# 611_jetbot_010210.net
KiCad netlist of a schematic drawn in EAGLE
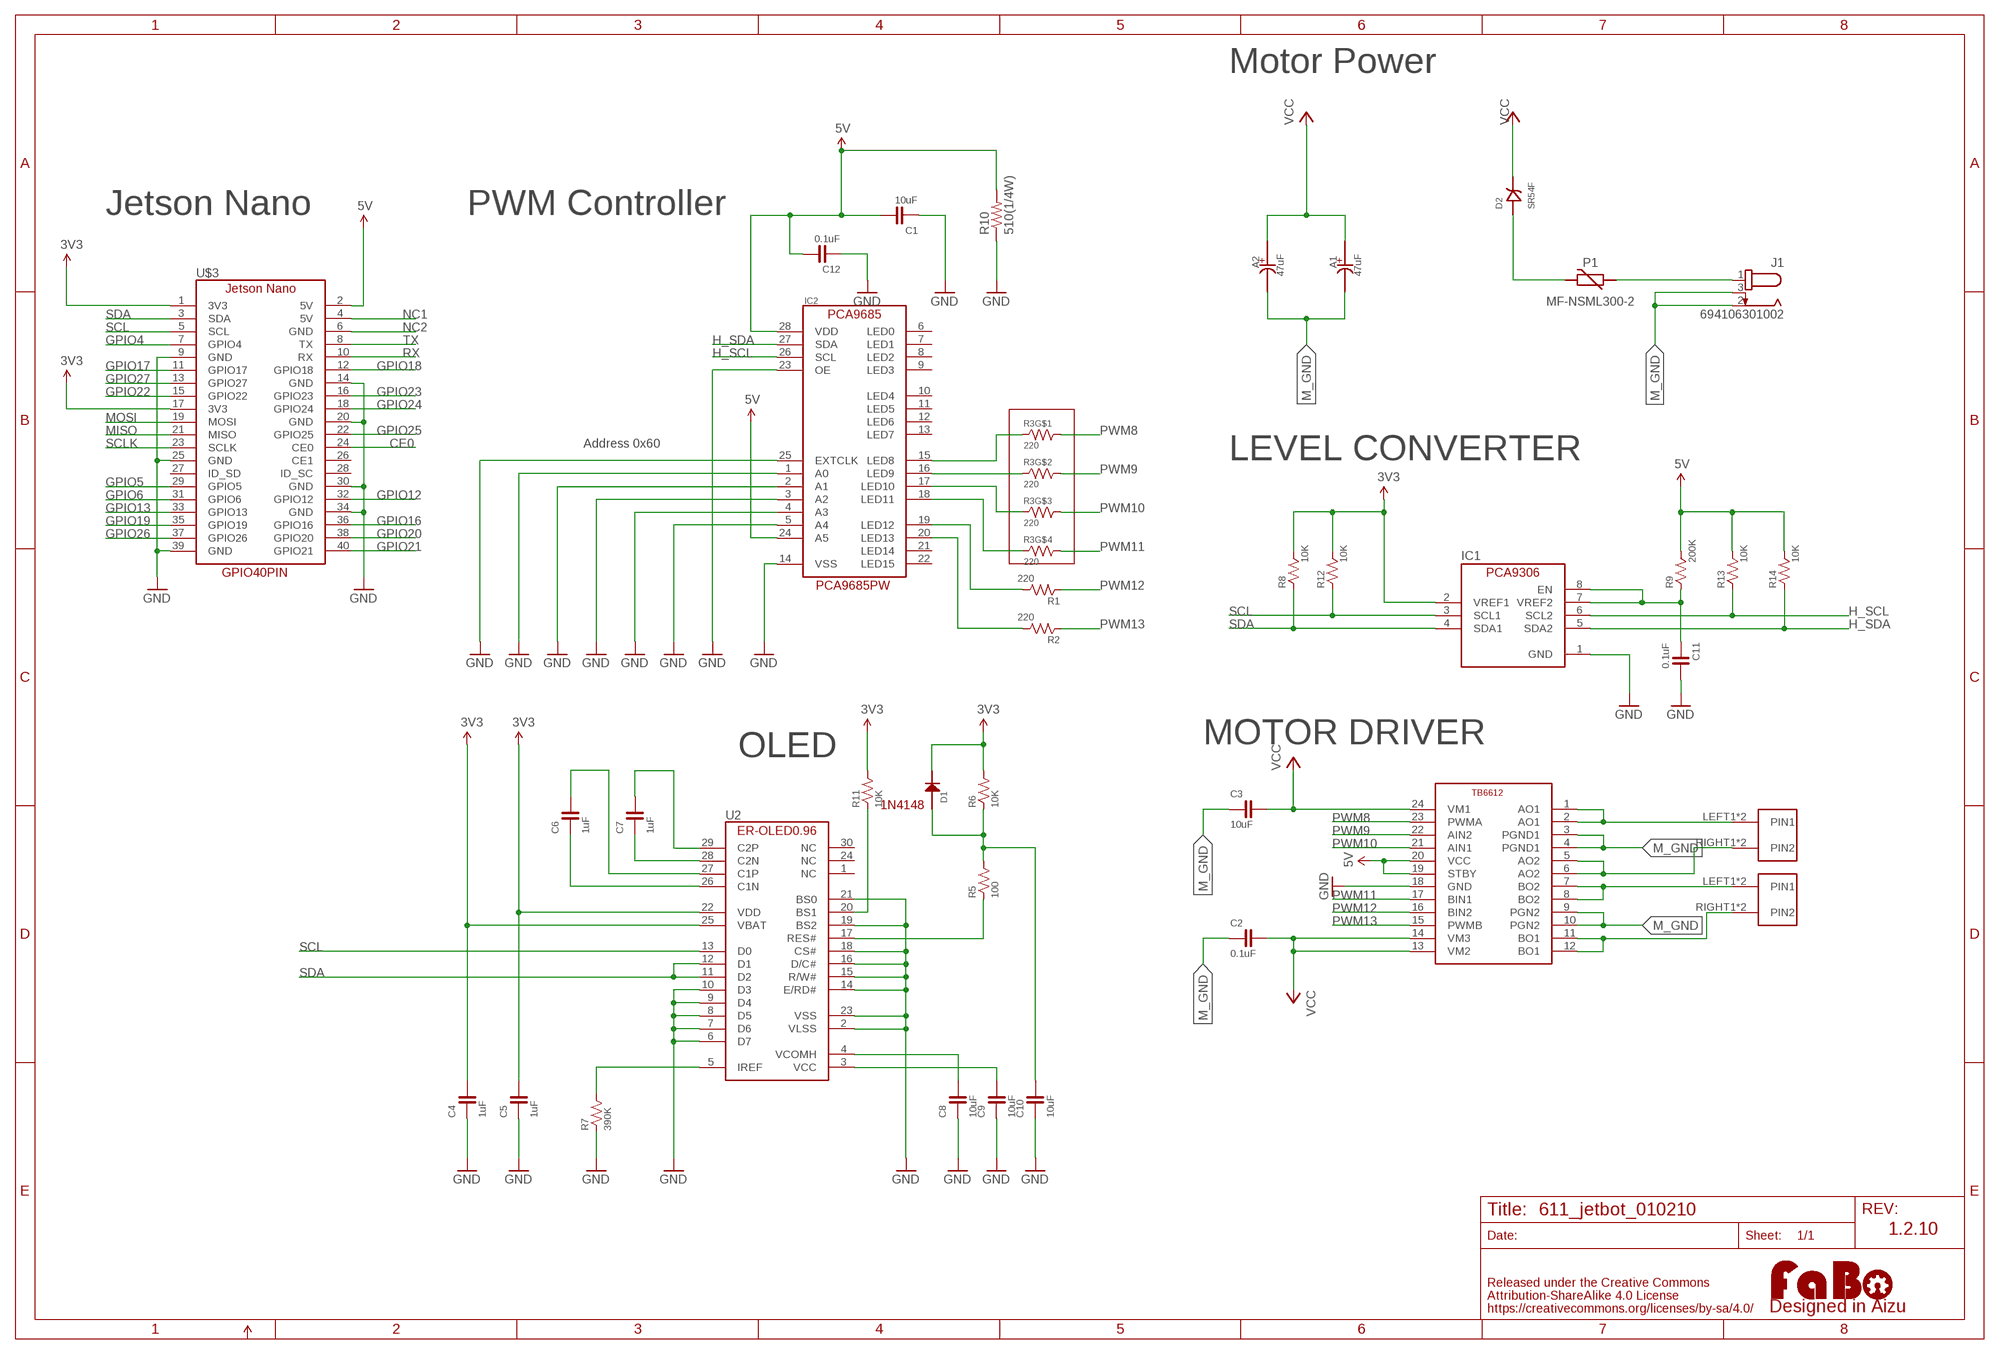
[diagram p0: schematic, sheet 1]

(export (version "E")
  (design (tool "Eeschema 10.0.6"))
  (components
    (comp (ref "A1")
      (value "47uF")
      (footprint "eagle-import:D60")
      (libsource (lib "eagle-import") (part "CAPACITOR-ALUMIN_D60"))
    )
    (comp (ref "A2")
      (value "47uF")
      (footprint "eagle-import:D60")
      (libsource (lib "eagle-import") (part "CAPACITOR-ALUMIN_D60"))
    )
    (comp (ref "C1")
      (value "10uF")
      (footprint "eagle-import:0603")
      (libsource (lib "eagle-import") (part "CAPACITOR-0603"))
    )
    (comp (ref "C2")
      (value "0.1uF")
      (footprint "eagle-import:0603")
      (libsource (lib "eagle-import") (part "CAPACITOR-0603"))
    )
    (comp (ref "C3")
      (value "10uF")
      (footprint "eagle-import:0603")
      (libsource (lib "eagle-import") (part "CAPACITOR-0603"))
    )
    (comp (ref "C4")
      (value "1uF")
      (footprint "eagle-import:0603-BOTTOM")
      (libsource (lib "eagle-import") (part "CAPACITOR-0603-BOTTOM"))
    )
    (comp (ref "C5")
      (value "1uF")
      (footprint "eagle-import:0603-BOTTOM")
      (libsource (lib "eagle-import") (part "CAPACITOR-0603-BOTTOM"))
    )
    (comp (ref "C6")
      (value "1uF")
      (footprint "eagle-import:0603-BOTTOM")
      (libsource (lib "eagle-import") (part "CAPACITOR-0603-BOTTOM"))
    )
    (comp (ref "C7")
      (value "1uF")
      (footprint "eagle-import:0603-BOTTOM")
      (libsource (lib "eagle-import") (part "CAPACITOR-0603-BOTTOM"))
    )
    (comp (ref "C8")
      (value "10uF")
      (footprint "eagle-import:0603-BOTTOM")
      (libsource (lib "eagle-import") (part "CAPACITOR-0603-BOTTOM"))
    )
    (comp (ref "C9")
      (value "10uF")
      (footprint "eagle-import:0603-BOTTOM")
      (libsource (lib "eagle-import") (part "CAPACITOR-0603-BOTTOM"))
    )
    (comp (ref "C10")
      (value "10uF")
      (footprint "eagle-import:0603-BOTTOM")
      (libsource (lib "eagle-import") (part "CAPACITOR-0603-BOTTOM"))
    )
    (comp (ref "C11")
      (value "0.1uF")
      (footprint "eagle-import:0603")
      (libsource (lib "eagle-import") (part "CAPACITOR-0603"))
    )
    (comp (ref "C12")
      (value "0.1uF")
      (footprint "eagle-import:0603")
      (libsource (lib "eagle-import") (part "CAPACITOR-0603"))
    )
    (comp (ref "D1")
      (value "1N4148")
      (footprint "eagle-import:1N4148W")
      (libsource (lib "eagle-import") (part "1N4148"))
    )
    (comp (ref "D2")
      (value "SR54F")
      (footprint "eagle-import:SMBF")
      (libsource (lib "eagle-import") (part "SR54F"))
    )
    (comp (ref "IC1")
      (value "PCA9306_SSOP")
      (footprint "eagle-import:8PIN-SSOP")
      (libsource (lib "eagle-import") (part "PCA9306_SSOP"))
    )
    (comp (ref "IC2")
      (value "PCA9685PW,BS")
      (footprint "eagle-import:PCA9685")
      (libsource (lib "eagle-import") (part "PCA9685PW,BS"))
    )
    (comp (ref "J1")
      (value "694106301002")
      (footprint "eagle-import:694106301002")
      (fields
        (field (name "DIGIKEY_PART_NUMBER") "732-5930-ND")
        (field (name "MANUFACTURER") "Wurth Electronics Inc.")
        (field (name "CREATED_BY") "PCBLayout.com")
      )
      (libsource (lib "eagle-import") (part "694106301002"))
    )
    (comp (ref "LOGO1")
      (value "LOGO_FABO-M")
      (footprint "eagle-import:LOGO_FABO_M")
      (libsource (lib "eagle-import") (part "LOGO_FABO-M"))
    )
    (comp (ref "P1")
      (value "MF-NSML300-2")
      (footprint "eagle-import:1206")
      (libsource (lib "eagle-import") (part "POLYSWITCH1206"))
    )
    (comp (ref "R1")
      (value "220")
      (footprint "eagle-import:0603")
      (libsource (lib "eagle-import") (part "RESISTOR-0603"))
    )
    (comp (ref "R2")
      (value "220")
      (footprint "eagle-import:0603")
      (libsource (lib "eagle-import") (part "RESISTOR-0603"))
    )
    (comp (ref "R3")
      (value "220")
      (footprint "eagle-import:EXBV8V")
      (libsource (lib "eagle-import") (part "RESISTOR_ARRAY"))
    )
    (comp (ref "R5")
      (value "100")
      (footprint "eagle-import:0603-BOTTOM")
      (libsource (lib "eagle-import") (part "RESISTOR-0603-BOTTOM"))
    )
    (comp (ref "R6")
      (value "10K")
      (footprint "eagle-import:0603-BOTTOM")
      (libsource (lib "eagle-import") (part "RESISTOR-0603-BOTTOM"))
    )
    (comp (ref "R7")
      (value "390K")
      (footprint "eagle-import:0603-BOTTOM")
      (libsource (lib "eagle-import") (part "RESISTOR-0603-BOTTOM"))
    )
    (comp (ref "R8")
      (value "10K")
      (footprint "eagle-import:0603")
      (libsource (lib "eagle-import") (part "RESISTOR-0603"))
    )
    (comp (ref "R9")
      (value "200K")
      (footprint "eagle-import:0603")
      (libsource (lib "eagle-import") (part "RESISTOR-0603"))
    )
    (comp (ref "R10")
      (value "510(1/4W)")
      (footprint "eagle-import:R0805")
      (libsource (lib "eagle-import") (part "R-US_R0805"))
    )
    (comp (ref "R11")
      (value "10K")
      (footprint "eagle-import:0603-BOTTOM")
      (libsource (lib "eagle-import") (part "RESISTOR-0603-BOTTOM"))
    )
    (comp (ref "R12")
      (value "10K")
      (footprint "eagle-import:0603")
      (libsource (lib "eagle-import") (part "RESISTOR-0603"))
    )
    (comp (ref "R13")
      (value "10K")
      (footprint "eagle-import:0603")
      (libsource (lib "eagle-import") (part "RESISTOR-0603"))
    )
    (comp (ref "R14")
      (value "10K")
      (footprint "eagle-import:0603")
      (libsource (lib "eagle-import") (part "RESISTOR-0603"))
    )
    (comp (ref "U$3")
      (value "JETSON_NANO")
      (footprint "eagle-import:JETSON_NANO")
      (libsource (lib "eagle-import") (part "JETSON_NANO"))
    )
    (comp (ref "U$5")
      (value "TB6612")
      (footprint "eagle-import:TB6612")
      (libsource (lib "eagle-import") (part "TB6612"))
    )
    (comp (ref "U$6")
      (value "ML-1400-S1")
      (footprint "eagle-import:ML-1400-S1")
      (libsource (lib "eagle-import") (part "ML-1400-S1"))
    )
    (comp (ref "U$8")
      (value "ML-1400-S1")
      (footprint "eagle-import:ML-1400-S1")
      (libsource (lib "eagle-import") (part "ML-1400-S1"))
    )
    (comp (ref "U2")
      (value "ER-OLED0.96-1ER-CON30HT-1_REV2")
      (footprint "eagle-import:ER-CON30HT-1_REV2")
      (libsource (lib "eagle-import") (part "ER-OLED0.96-1ER-CON30HT-1_REV2"))
    )
  )
  (nets
    (net (code "1") (name "/CE0") (class "Default")
      (node (ref "U$3") (pin "24") (pinfunction "CE0_24") (pintype "bidirectional"))
    )
    (net (code "2") (name "/GPIO4") (class "Default")
      (node (ref "U$3") (pin "7") (pinfunction "GPIO4_7") (pintype "bidirectional"))
    )
    (net (code "3") (name "/GPIO5") (class "Default")
      (node (ref "U$3") (pin "29") (pinfunction "GPIO5_29") (pintype "bidirectional"))
    )
    (net (code "4") (name "/GPIO6") (class "Default")
      (node (ref "U$3") (pin "31") (pinfunction "GPIO6_31") (pintype "bidirectional"))
    )
    (net (code "5") (name "/GPIO12") (class "Default")
      (node (ref "U$3") (pin "32") (pinfunction "GPIO12_32") (pintype "bidirectional"))
    )
    (net (code "6") (name "/GPIO13") (class "Default")
      (node (ref "U$3") (pin "33") (pinfunction "GPIO13_33") (pintype "bidirectional"))
    )
    (net (code "7") (name "/GPIO16") (class "Default")
      (node (ref "U$3") (pin "36") (pinfunction "GPIO16_36") (pintype "bidirectional"))
    )
    (net (code "8") (name "/GPIO17") (class "Default")
      (node (ref "U$3") (pin "11") (pinfunction "GPIO17_11") (pintype "bidirectional"))
    )
    (net (code "9") (name "/GPIO18") (class "Default")
      (node (ref "U$3") (pin "12") (pinfunction "GPIO18_12") (pintype "bidirectional"))
    )
    (net (code "10") (name "/GPIO19") (class "Default")
      (node (ref "U$3") (pin "35") (pinfunction "GPIO19_35") (pintype "bidirectional"))
    )
    (net (code "11") (name "/GPIO20") (class "Default")
      (node (ref "U$3") (pin "38") (pinfunction "GPIO20_38") (pintype "bidirectional"))
    )
    (net (code "12") (name "/GPIO21") (class "Default")
      (node (ref "U$3") (pin "40") (pinfunction "GPIO21_40") (pintype "bidirectional"))
    )
    (net (code "13") (name "/GPIO22") (class "Default")
      (node (ref "U$3") (pin "15") (pinfunction "GPIO22_15") (pintype "bidirectional"))
    )
    (net (code "14") (name "/GPIO23") (class "Default")
      (node (ref "U$3") (pin "16") (pinfunction "GPIO23_16") (pintype "bidirectional"))
    )
    (net (code "15") (name "/GPIO24") (class "Default")
      (node (ref "U$3") (pin "18") (pinfunction "GPIO24_18") (pintype "bidirectional"))
    )
    (net (code "16") (name "/GPIO25") (class "Default")
      (node (ref "U$3") (pin "22") (pinfunction "GPIO25_22") (pintype "bidirectional"))
    )
    (net (code "17") (name "/GPIO26") (class "Default")
      (node (ref "U$3") (pin "37") (pinfunction "GPIO26_37") (pintype "bidirectional"))
    )
    (net (code "18") (name "/GPIO27") (class "Default")
      (node (ref "U$3") (pin "13") (pinfunction "GPIO27_13") (pintype "bidirectional"))
    )
    (net (code "19") (name "/H_SCL") (class "Default")
      (node (ref "IC1") (pin "6") (pinfunction "SCL2_6") (pintype "bidirectional"))
      (node (ref "IC2") (pin "26") (pinfunction "SCL_26") (pintype "bidirectional"))
      (node (ref "R13") (pin "1") (pinfunction "1_1") (pintype "bidirectional"))
    )
    (net (code "20") (name "/H_SDA") (class "Default")
      (node (ref "IC1") (pin "5") (pinfunction "SDA2_5") (pintype "bidirectional"))
      (node (ref "IC2") (pin "27") (pinfunction "SDA_27") (pintype "bidirectional"))
      (node (ref "R14") (pin "1") (pinfunction "1_1") (pintype "bidirectional"))
    )
    (net (code "21") (name "/MISO") (class "Default")
      (node (ref "U$3") (pin "21") (pinfunction "MISO_21") (pintype "bidirectional"))
    )
    (net (code "22") (name "/MOSI") (class "Default")
      (node (ref "U$3") (pin "19") (pinfunction "MOSI_19") (pintype "bidirectional"))
    )
    (net (code "23") (name "/NC1") (class "Default")
      (node (ref "U$3") (pin "4") (pinfunction "5V_4") (pintype "bidirectional"))
    )
    (net (code "24") (name "/NC2") (class "Default")
      (node (ref "U$3") (pin "6") (pinfunction "GND_6") (pintype "bidirectional"))
    )
    (net (code "25") (name "/PWM8") (class "Default")
      (node (ref "R3") (pin "8") (pinfunction "2_8") (pintype "bidirectional"))
      (node (ref "U$5") (pin "23") (pinfunction "PWMA_23") (pintype "bidirectional"))
    )
    (net (code "26") (name "/PWM9") (class "Default")
      (node (ref "R3") (pin "7") (pinfunction "2_7") (pintype "bidirectional"))
      (node (ref "U$5") (pin "22") (pinfunction "AIN2_22") (pintype "bidirectional"))
    )
    (net (code "27") (name "/PWM10") (class "Default")
      (node (ref "R3") (pin "6") (pinfunction "2_6") (pintype "bidirectional"))
      (node (ref "U$5") (pin "21") (pinfunction "AIN1_21") (pintype "bidirectional"))
    )
    (net (code "28") (name "/PWM11") (class "Default")
      (node (ref "R3") (pin "5") (pinfunction "2_5") (pintype "bidirectional"))
      (node (ref "U$5") (pin "17") (pinfunction "BIN1_17") (pintype "bidirectional"))
    )
    (net (code "29") (name "/PWM12") (class "Default")
      (node (ref "R1") (pin "1") (pinfunction "1_1") (pintype "bidirectional"))
      (node (ref "U$5") (pin "16") (pinfunction "BIN2_16") (pintype "bidirectional"))
    )
    (net (code "30") (name "/PWM13") (class "Default")
      (node (ref "R2") (pin "1") (pinfunction "1_1") (pintype "bidirectional"))
      (node (ref "U$5") (pin "15") (pinfunction "PWMB_15") (pintype "bidirectional"))
    )
    (net (code "31") (name "/RX") (class "Default")
      (node (ref "U$3") (pin "10") (pinfunction "RX_10") (pintype "bidirectional"))
    )
    (net (code "32") (name "/SCL") (class "Default")
      (node (ref "IC1") (pin "3") (pinfunction "SCL1_3") (pintype "bidirectional"))
      (node (ref "R12") (pin "1") (pinfunction "1_1") (pintype "bidirectional"))
      (node (ref "U$3") (pin "5") (pinfunction "SCL_5") (pintype "bidirectional"))
      (node (ref "U2") (pin "13") (pinfunction "D0_13") (pintype "bidirectional"))
    )
    (net (code "33") (name "/SCLK") (class "Default")
      (node (ref "U$3") (pin "23") (pinfunction "SCLK_23") (pintype "bidirectional"))
    )
    (net (code "34") (name "/SDA") (class "Default")
      (node (ref "IC1") (pin "4") (pinfunction "SDA1_4") (pintype "bidirectional"))
      (node (ref "R8") (pin "1") (pinfunction "1_1") (pintype "bidirectional"))
      (node (ref "U$3") (pin "3") (pinfunction "SDA_3") (pintype "bidirectional"))
      (node (ref "U2") (pin "11") (pinfunction "D2_11") (pintype "bidirectional"))
      (node (ref "U2") (pin "12") (pinfunction "D1_12") (pintype "bidirectional"))
    )
    (net (code "35") (name "/TX") (class "Default")
      (node (ref "U$3") (pin "8") (pinfunction "TX_8") (pintype "bidirectional"))
    )
    (net (code "36") (name "3V3") (class "Default")
      (node (ref "C4") (pin "2") (pinfunction "2_2") (pintype "passive"))
      (node (ref "C5") (pin "2") (pinfunction "2_2") (pintype "passive"))
      (node (ref "D1") (pin "CATHODE") (pinfunction "CATHODE_CATHODE") (pintype "bidirectional"))
      (node (ref "IC1") (pin "2") (pinfunction "VREF1_2") (pintype "bidirectional"))
      (node (ref "R11") (pin "2") (pinfunction "2_2") (pintype "bidirectional"))
      (node (ref "R12") (pin "2") (pinfunction "2_2") (pintype "bidirectional"))
      (node (ref "R6") (pin "2") (pinfunction "2_2") (pintype "bidirectional"))
      (node (ref "R8") (pin "2") (pinfunction "2_2") (pintype "bidirectional"))
      (node (ref "U$3") (pin "1") (pinfunction "3V3_1") (pintype "bidirectional"))
      (node (ref "U$3") (pin "17") (pinfunction "3V3_17") (pintype "bidirectional"))
      (node (ref "U2") (pin "22") (pinfunction "VDD_22") (pintype "bidirectional"))
      (node (ref "U2") (pin "25") (pinfunction "VBAT_25") (pintype "bidirectional"))
    )
    (net (code "37") (name "5V") (class "Default")
      (node (ref "C1") (pin "2") (pinfunction "2_2") (pintype "passive"))
      (node (ref "C12") (pin "2") (pinfunction "2_2") (pintype "passive"))
      (node (ref "IC2") (pin "24") (pinfunction "A5_24") (pintype "bidirectional"))
      (node (ref "IC2") (pin "28") (pinfunction "VDD_28") (pintype "bidirectional"))
      (node (ref "R10") (pin "2") (pinfunction "2_2") (pintype "passive"))
      (node (ref "R13") (pin "2") (pinfunction "2_2") (pintype "bidirectional"))
      (node (ref "R14") (pin "2") (pinfunction "2_2") (pintype "bidirectional"))
      (node (ref "R9") (pin "2") (pinfunction "2_2") (pintype "bidirectional"))
      (node (ref "U$3") (pin "2") (pinfunction "5V_2") (pintype "bidirectional"))
      (node (ref "U$5") (pin "19") (pinfunction "STBY_19") (pintype "bidirectional"))
      (node (ref "U$5") (pin "20") (pinfunction "VCC_20") (pintype "bidirectional"))
    )
    (net (code "38") (name "GND") (class "Default")
      (node (ref "C1") (pin "1") (pinfunction "1_1") (pintype "passive"))
      (node (ref "C10") (pin "1") (pinfunction "1_1") (pintype "passive"))
      (node (ref "C11") (pin "2") (pinfunction "2_2") (pintype "passive"))
      (node (ref "C12") (pin "1") (pinfunction "1_1") (pintype "passive"))
      (node (ref "C4") (pin "1") (pinfunction "1_1") (pintype "passive"))
      (node (ref "C5") (pin "1") (pinfunction "1_1") (pintype "passive"))
      (node (ref "C8") (pin "1") (pinfunction "1_1") (pintype "passive"))
      (node (ref "C9") (pin "1") (pinfunction "1_1") (pintype "passive"))
      (node (ref "IC1") (pin "1") (pinfunction "GND_1") (pintype "bidirectional"))
      (node (ref "IC2") (pin "1") (pinfunction "A0_1") (pintype "bidirectional"))
      (node (ref "IC2") (pin "14") (pinfunction "VSS_14") (pintype "bidirectional"))
      (node (ref "IC2") (pin "2") (pinfunction "A1_2") (pintype "bidirectional"))
      (node (ref "IC2") (pin "23") (pinfunction "OE_23") (pintype "bidirectional"))
      (node (ref "IC2") (pin "25") (pinfunction "EXTCLK_25") (pintype "bidirectional"))
      (node (ref "IC2") (pin "3") (pinfunction "A2_3") (pintype "bidirectional"))
      (node (ref "IC2") (pin "4") (pinfunction "A3_4") (pintype "bidirectional"))
      (node (ref "IC2") (pin "5") (pinfunction "A4_5") (pintype "bidirectional"))
      (node (ref "R10") (pin "1") (pinfunction "1_1") (pintype "passive"))
      (node (ref "R7") (pin "1") (pinfunction "1_1") (pintype "bidirectional"))
      (node (ref "U$3") (pin "14") (pinfunction "GND_14") (pintype "bidirectional"))
      (node (ref "U$3") (pin "20") (pinfunction "GND_20") (pintype "bidirectional"))
      (node (ref "U$3") (pin "25") (pinfunction "GND_25") (pintype "bidirectional"))
      (node (ref "U$3") (pin "30") (pinfunction "GND_30") (pintype "bidirectional"))
      (node (ref "U$3") (pin "34") (pinfunction "GND_34") (pintype "bidirectional"))
      (node (ref "U$3") (pin "39") (pinfunction "GND_39") (pintype "bidirectional"))
      (node (ref "U$3") (pin "9") (pinfunction "GND_9") (pintype "bidirectional"))
      (node (ref "U$5") (pin "18") (pinfunction "GND_18") (pintype "bidirectional"))
      (node (ref "U2") (pin "10") (pinfunction "D3_10") (pintype "bidirectional"))
      (node (ref "U2") (pin "14") (pinfunction "E/RD#_14") (pintype "bidirectional"))
      (node (ref "U2") (pin "15") (pinfunction "R/W#_15") (pintype "bidirectional"))
      (node (ref "U2") (pin "16") (pinfunction "D/C#_16") (pintype "bidirectional"))
      (node (ref "U2") (pin "18") (pinfunction "CS#_18") (pintype "bidirectional"))
      (node (ref "U2") (pin "19") (pinfunction "BS2_19") (pintype "bidirectional"))
      (node (ref "U2") (pin "2") (pinfunction "VLSS_2") (pintype "bidirectional"))
      (node (ref "U2") (pin "21") (pinfunction "BS0_21") (pintype "bidirectional"))
      (node (ref "U2") (pin "23") (pinfunction "VSS_23") (pintype "bidirectional"))
      (node (ref "U2") (pin "6") (pinfunction "D7_6") (pintype "bidirectional"))
      (node (ref "U2") (pin "7") (pinfunction "D6_7") (pintype "bidirectional"))
      (node (ref "U2") (pin "8") (pinfunction "D5_8") (pintype "bidirectional"))
      (node (ref "U2") (pin "9") (pinfunction "D4_9") (pintype "bidirectional"))
    )
    (net (code "39") (name "M_GND") (class "Default")
      (node (ref "A1") (pin "MINUS") (pinfunction "-_MINUS") (pintype "passive"))
      (node (ref "A2") (pin "MINUS") (pinfunction "-_MINUS") (pintype "passive"))
      (node (ref "C2") (pin "1") (pinfunction "1_1") (pintype "passive"))
      (node (ref "C3") (pin "1") (pinfunction "1_1") (pintype "passive"))
      (node (ref "J1") (pin "2") (pinfunction "2_2") (pintype "passive"))
      (node (ref "J1") (pin "3") (pinfunction "3_3") (pintype "passive"))
      (node (ref "U$5") (pin "10") (pinfunction "PGN2_10") (pintype "bidirectional"))
      (node (ref "U$5") (pin "3") (pinfunction "PGND1_3") (pintype "bidirectional"))
      (node (ref "U$5") (pin "4") (pinfunction "PGND1_4") (pintype "bidirectional"))
      (node (ref "U$5") (pin "9") (pinfunction "PGN2_9") (pintype "bidirectional"))
    )
    (net (code "40") (name "Net-(C10-Pad2)") (class "Default")
      (node (ref "C10") (pin "2") (pinfunction "2_2") (pintype "passive"))
      (node (ref "D1") (pin "ANODE") (pinfunction "ANODE_ANODE") (pintype "bidirectional"))
      (node (ref "R5") (pin "2") (pinfunction "2_2") (pintype "bidirectional"))
      (node (ref "R6") (pin "1") (pinfunction "1_1") (pintype "bidirectional"))
    )
    (net (code "41") (name "Net-(D2-PadANODE)") (class "Default")
      (node (ref "D2") (pin "ANODE") (pinfunction "ANODE_ANODE") (pintype "bidirectional"))
      (node (ref "P1") (pin "2") (pinfunction "2_2") (pintype "bidirectional"))
    )
    (net (code "42") (name "Net-(IC1-EN)") (class "Default")
      (node (ref "C11") (pin "1") (pinfunction "1_1") (pintype "passive"))
      (node (ref "IC1") (pin "7") (pinfunction "VREF2_7") (pintype "bidirectional"))
      (node (ref "IC1") (pin "8") (pinfunction "EN_8") (pintype "bidirectional"))
      (node (ref "R9") (pin "1") (pinfunction "1_1") (pintype "bidirectional"))
    )
    (net (code "43") (name "Net-(IC2-LED8)") (class "Default")
      (node (ref "IC2") (pin "15") (pinfunction "LED8_15") (pintype "bidirectional"))
      (node (ref "R3") (pin "1") (pinfunction "1_1") (pintype "bidirectional"))
    )
    (net (code "44") (name "Net-(IC2-LED9)") (class "Default")
      (node (ref "IC2") (pin "16") (pinfunction "LED9_16") (pintype "bidirectional"))
      (node (ref "R3") (pin "2") (pinfunction "1_2") (pintype "bidirectional"))
    )
    (net (code "45") (name "Net-(IC2-LED10)") (class "Default")
      (node (ref "IC2") (pin "17") (pinfunction "LED10_17") (pintype "bidirectional"))
      (node (ref "R3") (pin "3") (pinfunction "1_3") (pintype "bidirectional"))
    )
    (net (code "46") (name "Net-(IC2-LED11)") (class "Default")
      (node (ref "IC2") (pin "18") (pinfunction "LED11_18") (pintype "bidirectional"))
      (node (ref "R3") (pin "4") (pinfunction "1_4") (pintype "bidirectional"))
    )
    (net (code "47") (name "Net-(IC2-LED12)") (class "Default")
      (node (ref "IC2") (pin "19") (pinfunction "LED12_19") (pintype "bidirectional"))
      (node (ref "R1") (pin "2") (pinfunction "2_2") (pintype "bidirectional"))
    )
    (net (code "48") (name "Net-(IC2-LED13)") (class "Default")
      (node (ref "IC2") (pin "20") (pinfunction "LED13_20") (pintype "bidirectional"))
      (node (ref "R2") (pin "2") (pinfunction "2_2") (pintype "bidirectional"))
    )
    (net (code "49") (name "Net-(J1-Pad1)") (class "Default")
      (node (ref "J1") (pin "1") (pinfunction "1_1") (pintype "passive"))
      (node (ref "P1") (pin "1") (pinfunction "1_1") (pintype "bidirectional"))
    )
    (net (code "50") (name "Net-(U$5-AO1-Pad1)") (class "Default")
      (node (ref "U$5") (pin "1") (pinfunction "AO1_1") (pintype "bidirectional"))
      (node (ref "U$5") (pin "2") (pinfunction "AO1_2") (pintype "bidirectional"))
      (node (ref "U$6") (pin "LEFT1") (pinfunction "PIN1_LEFT1") (pintype "bidirectional"))
      (node (ref "U$6") (pin "LEFT2") (pinfunction "PIN1_LEFT2") (pintype "bidirectional"))
    )
    (net (code "51") (name "Net-(U$5-AO2-Pad5)") (class "Default")
      (node (ref "U$5") (pin "5") (pinfunction "AO2_5") (pintype "bidirectional"))
      (node (ref "U$5") (pin "6") (pinfunction "AO2_6") (pintype "bidirectional"))
      (node (ref "U$6") (pin "RIGHT1") (pinfunction "PIN2_RIGHT1") (pintype "bidirectional"))
      (node (ref "U$6") (pin "RIGHT2") (pinfunction "PIN2_RIGHT2") (pintype "bidirectional"))
    )
    (net (code "52") (name "Net-(U$5-BO1-Pad11)") (class "Default")
      (node (ref "U$5") (pin "11") (pinfunction "BO1_11") (pintype "bidirectional"))
      (node (ref "U$5") (pin "12") (pinfunction "BO1_12") (pintype "bidirectional"))
      (node (ref "U$8") (pin "RIGHT1") (pinfunction "PIN2_RIGHT1") (pintype "bidirectional"))
      (node (ref "U$8") (pin "RIGHT2") (pinfunction "PIN2_RIGHT2") (pintype "bidirectional"))
    )
    (net (code "53") (name "Net-(U$5-BO2-Pad7)") (class "Default")
      (node (ref "U$5") (pin "7") (pinfunction "BO2_7") (pintype "bidirectional"))
      (node (ref "U$5") (pin "8") (pinfunction "BO2_8") (pintype "bidirectional"))
      (node (ref "U$8") (pin "LEFT1") (pinfunction "PIN1_LEFT1") (pintype "bidirectional"))
      (node (ref "U$8") (pin "LEFT2") (pinfunction "PIN1_LEFT2") (pintype "bidirectional"))
    )
    (net (code "54") (name "Net-(U2-BS1)") (class "Default")
      (node (ref "R11") (pin "1") (pinfunction "1_1") (pintype "bidirectional"))
      (node (ref "U2") (pin "20") (pinfunction "BS1_20") (pintype "bidirectional"))
    )
    (net (code "55") (name "Net-(U2-C1N)") (class "Default")
      (node (ref "C6") (pin "1") (pinfunction "1_1") (pintype "passive"))
      (node (ref "U2") (pin "26") (pinfunction "C1N_26") (pintype "bidirectional"))
    )
    (net (code "56") (name "Net-(U2-C1P)") (class "Default")
      (node (ref "C6") (pin "2") (pinfunction "2_2") (pintype "passive"))
      (node (ref "U2") (pin "27") (pinfunction "C1P_27") (pintype "bidirectional"))
    )
    (net (code "57") (name "Net-(U2-C2N)") (class "Default")
      (node (ref "C7") (pin "1") (pinfunction "1_1") (pintype "passive"))
      (node (ref "U2") (pin "28") (pinfunction "C2N_28") (pintype "bidirectional"))
    )
    (net (code "58") (name "Net-(U2-C2P)") (class "Default")
      (node (ref "C7") (pin "2") (pinfunction "2_2") (pintype "passive"))
      (node (ref "U2") (pin "29") (pinfunction "C2P_29") (pintype "bidirectional"))
    )
    (net (code "59") (name "Net-(U2-IREF)") (class "Default")
      (node (ref "R7") (pin "2") (pinfunction "2_2") (pintype "bidirectional"))
      (node (ref "U2") (pin "5") (pinfunction "IREF_5") (pintype "bidirectional"))
    )
    (net (code "60") (name "Net-(U2-RES#)") (class "Default")
      (node (ref "R5") (pin "1") (pinfunction "1_1") (pintype "bidirectional"))
      (node (ref "U2") (pin "17") (pinfunction "RES#_17") (pintype "bidirectional"))
    )
    (net (code "61") (name "Net-(U2-VCC)") (class "Default")
      (node (ref "C9") (pin "2") (pinfunction "2_2") (pintype "passive"))
      (node (ref "U2") (pin "3") (pinfunction "VCC_3") (pintype "bidirectional"))
    )
    (net (code "62") (name "Net-(U2-VCOMH)") (class "Default")
      (node (ref "C8") (pin "2") (pinfunction "2_2") (pintype "passive"))
      (node (ref "U2") (pin "4") (pinfunction "VCOMH_4") (pintype "bidirectional"))
    )
    (net (code "63") (name "VCC") (class "Default")
      (node (ref "A1") (pin "PLUS") (pinfunction "+_PLUS") (pintype "passive"))
      (node (ref "A2") (pin "PLUS") (pinfunction "+_PLUS") (pintype "passive"))
      (node (ref "C2") (pin "2") (pinfunction "2_2") (pintype "passive"))
      (node (ref "C3") (pin "2") (pinfunction "2_2") (pintype "passive"))
      (node (ref "D2") (pin "CATHODE") (pinfunction "CATHODE_CATHODE") (pintype "bidirectional"))
      (node (ref "U$5") (pin "13") (pinfunction "VM2_13") (pintype "bidirectional"))
      (node (ref "U$5") (pin "14") (pinfunction "VM3_14") (pintype "bidirectional"))
      (node (ref "U$5") (pin "24") (pinfunction "VM1_24") (pintype "bidirectional"))
    )
    (net (code "64") (name "unconnected-(IC2-LED0-Pad6)") (class "Default")
      (node (ref "IC2") (pin "6") (pinfunction "LED0_6") (pintype "bidirectional"))
    )
    (net (code "65") (name "unconnected-(IC2-LED1-Pad7)") (class "Default")
      (node (ref "IC2") (pin "7") (pinfunction "LED1_7") (pintype "bidirectional"))
    )
    (net (code "66") (name "unconnected-(IC2-LED2-Pad8)") (class "Default")
      (node (ref "IC2") (pin "8") (pinfunction "LED2_8") (pintype "bidirectional"))
    )
    (net (code "67") (name "unconnected-(IC2-LED3-Pad9)") (class "Default")
      (node (ref "IC2") (pin "9") (pinfunction "LED3_9") (pintype "bidirectional"))
    )
    (net (code "68") (name "unconnected-(IC2-LED4-Pad10)") (class "Default")
      (node (ref "IC2") (pin "10") (pinfunction "LED4_10") (pintype "bidirectional"))
    )
    (net (code "69") (name "unconnected-(IC2-LED5-Pad11)") (class "Default")
      (node (ref "IC2") (pin "11") (pinfunction "LED5_11") (pintype "bidirectional"))
    )
    (net (code "70") (name "unconnected-(IC2-LED6-Pad12)") (class "Default")
      (node (ref "IC2") (pin "12") (pinfunction "LED6_12") (pintype "bidirectional"))
    )
    (net (code "71") (name "unconnected-(IC2-LED7-Pad13)") (class "Default")
      (node (ref "IC2") (pin "13") (pinfunction "LED7_13") (pintype "bidirectional"))
    )
    (net (code "72") (name "unconnected-(IC2-LED14-Pad21)") (class "Default")
      (node (ref "IC2") (pin "21") (pinfunction "LED14_21") (pintype "bidirectional"))
    )
    (net (code "73") (name "unconnected-(IC2-LED15-Pad22)") (class "Default")
      (node (ref "IC2") (pin "22") (pinfunction "LED15_22") (pintype "bidirectional"))
    )
    (net (code "74") (name "unconnected-(U$3-CE1-Pad26)") (class "Default")
      (node (ref "U$3") (pin "26") (pinfunction "CE1_26") (pintype "bidirectional"))
    )
    (net (code "75") (name "unconnected-(U$3-ID_SC-Pad28)") (class "Default")
      (node (ref "U$3") (pin "28") (pinfunction "ID_SC_28") (pintype "bidirectional"))
    )
    (net (code "76") (name "unconnected-(U$3-ID_SD-Pad27)") (class "Default")
      (node (ref "U$3") (pin "27") (pinfunction "ID_SD_27") (pintype "bidirectional"))
    )
    (net (code "77") (name "unconnected-(U2-NC-Pad1)") (class "Default")
      (node (ref "U2") (pin "1") (pinfunction "NC_1") (pintype "bidirectional"))
    )
    (net (code "78") (name "unconnected-(U2-NC-Pad24)") (class "Default")
      (node (ref "U2") (pin "24") (pinfunction "NC_24") (pintype "bidirectional"))
    )
    (net (code "79") (name "unconnected-(U2-NC-Pad30)") (class "Default")
      (node (ref "U2") (pin "30") (pinfunction "NC_30") (pintype "bidirectional"))
    )
  )
)
